# TTP.net
KiCad netlist of a schematic drawn in Altium Designer
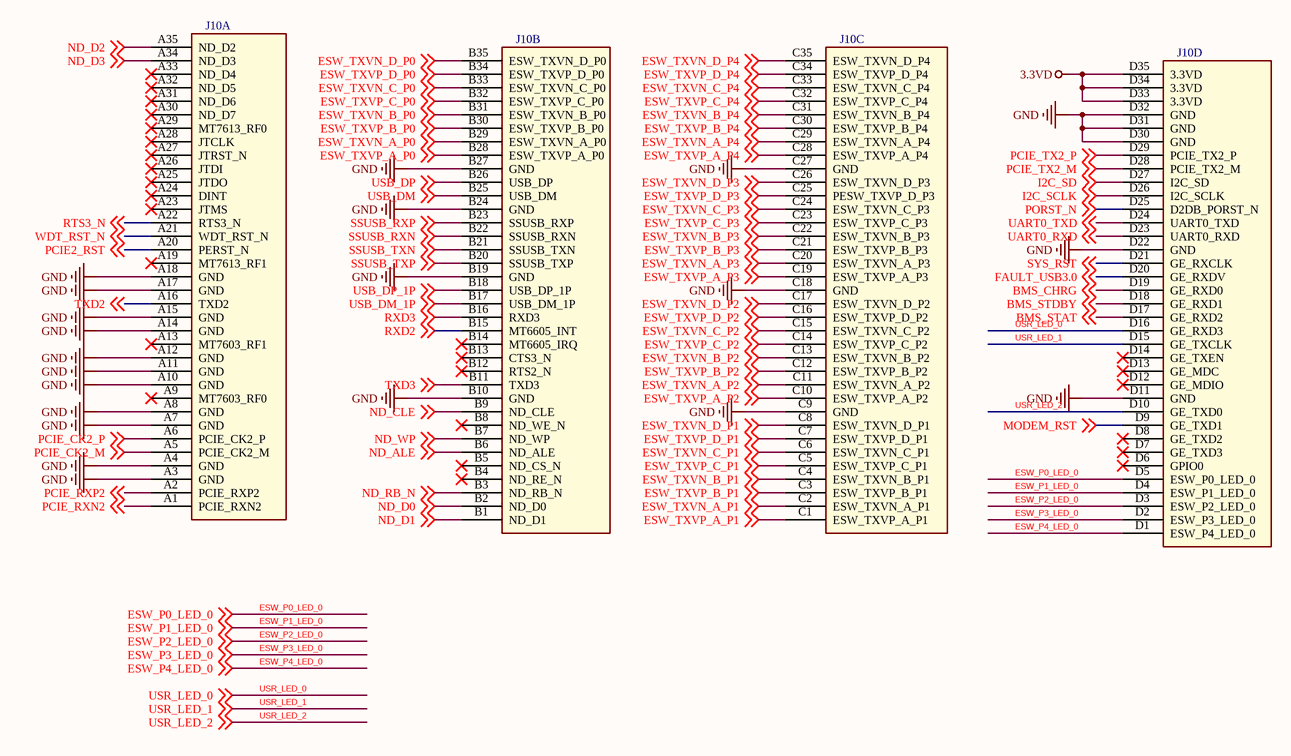
[diagram p0: TTP.SchDoc]

(export (version "E")
  (design (tool "Eeschema 10.0.6"))
  (components
    (comp (ref "J10") (value "SoM") (footprint "SoM") (libsource (lib "IIOT_GATEWAY_MT7621") (part "SoM")))
  )
  (nets
    (net (code "1") (name "3.3VD") (class "Default")
      (node (ref "J10") (pin "D33") (pinfunction "3.3VD_D33") (pintype "passive"))
      (node (ref "J10") (pin "D34") (pinfunction "3.3VD_D34") (pintype "passive"))
      (node (ref "J10") (pin "D35") (pinfunction "3.3VD_D35") (pintype "passive"))
    )
    (net (code "2") (name "BMS_CHRG") (class "Default")
      (node (ref "J10") (pin "D19") (pinfunction "GE_RXD0_D19") (pintype "passive"))
    )
    (net (code "3") (name "BMS_STAT") (class "Default")
      (node (ref "J10") (pin "D17") (pinfunction "GE_RXD2_D17") (pintype "passive"))
    )
    (net (code "4") (name "BMS_STDBY") (class "Default")
      (node (ref "J10") (pin "D18") (pinfunction "GE_RXD1_D18") (pintype "passive"))
    )
    (net (code "5") (name "ESW_P0_LED_0") (class "Default")
      (node (ref "J10") (pin "D5") (pinfunction "ESW_P0_LED_0_D5") (pintype "passive"))
    )
    (net (code "6") (name "ESW_P1_LED_0") (class "Default")
      (node (ref "J10") (pin "D4") (pinfunction "ESW_P1_LED_0_D4") (pintype "passive"))
    )
    (net (code "7") (name "ESW_P2_LED_0") (class "Default")
      (node (ref "J10") (pin "D3") (pinfunction "ESW_P2_LED_0_D3") (pintype "passive"))
    )
    (net (code "8") (name "ESW_P3_LED_0") (class "Default")
      (node (ref "J10") (pin "D2") (pinfunction "ESW_P3_LED_0_D2") (pintype "passive"))
    )
    (net (code "9") (name "ESW_P4_LED_0") (class "Default")
      (node (ref "J10") (pin "D1") (pinfunction "ESW_P4_LED_0_D1") (pintype "passive"))
    )
    (net (code "10") (name "ESW_TXVN_A_P0") (class "Default")
      (node (ref "J10") (pin "B29") (pinfunction "ESW_TXVN_A_P0_B29") (pintype "passive"))
    )
    (net (code "11") (name "ESW_TXVN_A_P1") (class "Default")
      (node (ref "J10") (pin "C2") (pinfunction "ESW_TXVN_A_P1_C2") (pintype "passive"))
    )
    (net (code "12") (name "ESW_TXVN_A_P2") (class "Default")
      (node (ref "J10") (pin "C11") (pinfunction "ESW_TXVN_A_P2_C11") (pintype "passive"))
    )
    (net (code "13") (name "ESW_TXVN_A_P3") (class "Default")
      (node (ref "J10") (pin "C20") (pinfunction "ESW_TXVN_A_P3_C20") (pintype "passive"))
    )
    (net (code "14") (name "ESW_TXVN_A_P4") (class "Default")
      (node (ref "J10") (pin "C29") (pinfunction "ESW_TXVN_A_P4_C29") (pintype "passive"))
    )
    (net (code "15") (name "ESW_TXVN_B_P0") (class "Default")
      (node (ref "J10") (pin "B31") (pinfunction "ESW_TXVN_B_P0_B31") (pintype "passive"))
    )
    (net (code "16") (name "ESW_TXVN_B_P1") (class "Default")
      (node (ref "J10") (pin "C4") (pinfunction "ESW_TXVN_B_P1_C4") (pintype "passive"))
    )
    (net (code "17") (name "ESW_TXVN_B_P2") (class "Default")
      (node (ref "J10") (pin "C13") (pinfunction "ESW_TXVN_B_P2_C13") (pintype "passive"))
    )
    (net (code "18") (name "ESW_TXVN_B_P3") (class "Default")
      (node (ref "J10") (pin "C22") (pinfunction "ESW_TXVN_B_P3_C22") (pintype "passive"))
    )
    (net (code "19") (name "ESW_TXVN_B_P4") (class "Default")
      (node (ref "J10") (pin "C31") (pinfunction "ESW_TXVN_B_P4_C31") (pintype "passive"))
    )
    (net (code "20") (name "ESW_TXVN_C_P0") (class "Default")
      (node (ref "J10") (pin "B33") (pinfunction "ESW_TXVN_C_P0_B33") (pintype "passive"))
    )
    (net (code "21") (name "ESW_TXVN_C_P1") (class "Default")
      (node (ref "J10") (pin "C6") (pinfunction "ESW_TXVN_C_P1_C6") (pintype "passive"))
    )
    (net (code "22") (name "ESW_TXVN_C_P2") (class "Default")
      (node (ref "J10") (pin "C15") (pinfunction "ESW_TXVN_C_P2_C15") (pintype "passive"))
    )
    (net (code "23") (name "ESW_TXVN_C_P3") (class "Default")
      (node (ref "J10") (pin "C24") (pinfunction "ESW_TXVN_C_P3_C24") (pintype "passive"))
    )
    (net (code "24") (name "ESW_TXVN_C_P4") (class "Default")
      (node (ref "J10") (pin "C33") (pinfunction "ESW_TXVN_C_P4_C33") (pintype "passive"))
    )
    (net (code "25") (name "ESW_TXVN_D_P0") (class "Default")
      (node (ref "J10") (pin "B35") (pinfunction "ESW_TXVN_D_P0_B35") (pintype "passive"))
    )
    (net (code "26") (name "ESW_TXVN_D_P1") (class "Default")
      (node (ref "J10") (pin "C8") (pinfunction "ESW_TXVN_D_P1_C8") (pintype "passive"))
    )
    (net (code "27") (name "ESW_TXVN_D_P2") (class "Default")
      (node (ref "J10") (pin "C17") (pinfunction "ESW_TXVN_D_P2_C17") (pintype "passive"))
    )
    (net (code "28") (name "ESW_TXVN_D_P3") (class "Default")
      (node (ref "J10") (pin "C26") (pinfunction "ESW_TXVN_D_P3_C26") (pintype "passive"))
    )
    (net (code "29") (name "ESW_TXVN_D_P4") (class "Default")
      (node (ref "J10") (pin "C35") (pinfunction "ESW_TXVN_D_P4_C35") (pintype "passive"))
    )
    (net (code "30") (name "ESW_TXVP_A_P0") (class "Default")
      (node (ref "J10") (pin "B28") (pinfunction "ESW_TXVP_A_P0_B28") (pintype "passive"))
    )
    (net (code "31") (name "ESW_TXVP_A_P1") (class "Default")
      (node (ref "J10") (pin "C1") (pinfunction "ESW_TXVP_A_P1_C1") (pintype "passive"))
    )
    (net (code "32") (name "ESW_TXVP_A_P2") (class "Default")
      (node (ref "J10") (pin "C10") (pinfunction "ESW_TXVP_A_P2_C10") (pintype "passive"))
    )
    (net (code "33") (name "ESW_TXVP_A_P3") (class "Default")
      (node (ref "J10") (pin "C19") (pinfunction "ESW_TXVP_A_P3_C19") (pintype "passive"))
    )
    (net (code "34") (name "ESW_TXVP_A_P4") (class "Default")
      (node (ref "J10") (pin "C28") (pinfunction "ESW_TXVP_A_P4_C28") (pintype "passive"))
    )
    (net (code "35") (name "ESW_TXVP_B_P0") (class "Default")
      (node (ref "J10") (pin "B30") (pinfunction "ESW_TXVP_B_P0_B30") (pintype "passive"))
    )
    (net (code "36") (name "ESW_TXVP_B_P1") (class "Default")
      (node (ref "J10") (pin "C3") (pinfunction "ESW_TXVP_B_P1_C3") (pintype "passive"))
    )
    (net (code "37") (name "ESW_TXVP_B_P2") (class "Default")
      (node (ref "J10") (pin "C12") (pinfunction "ESW_TXVP_B_P2_C12") (pintype "passive"))
    )
    (net (code "38") (name "ESW_TXVP_B_P3") (class "Default")
      (node (ref "J10") (pin "C21") (pinfunction "ESW_TXVP_B_P3_C21") (pintype "passive"))
    )
    (net (code "39") (name "ESW_TXVP_B_P4") (class "Default")
      (node (ref "J10") (pin "C30") (pinfunction "ESW_TXVP_B_P4_C30") (pintype "passive"))
    )
    (net (code "40") (name "ESW_TXVP_C_P0") (class "Default")
      (node (ref "J10") (pin "B32") (pinfunction "ESW_TXVP_C_P0_B32") (pintype "passive"))
    )
    (net (code "41") (name "ESW_TXVP_C_P1") (class "Default")
      (node (ref "J10") (pin "C5") (pinfunction "ESW_TXVP_C_P1_C5") (pintype "passive"))
    )
    (net (code "42") (name "ESW_TXVP_C_P2") (class "Default")
      (node (ref "J10") (pin "C14") (pinfunction "ESW_TXVP_C_P2_C14") (pintype "passive"))
    )
    (net (code "43") (name "ESW_TXVP_C_P3") (class "Default")
      (node (ref "J10") (pin "C23") (pinfunction "ESW_TXVP_C_P3_C23") (pintype "passive"))
    )
    (net (code "44") (name "ESW_TXVP_C_P4") (class "Default")
      (node (ref "J10") (pin "C32") (pinfunction "ESW_TXVP_C_P4_C32") (pintype "passive"))
    )
    (net (code "45") (name "ESW_TXVP_D_P0") (class "Default")
      (node (ref "J10") (pin "B34") (pinfunction "ESW_TXVP_D_P0_B34") (pintype "passive"))
    )
    (net (code "46") (name "ESW_TXVP_D_P1") (class "Default")
      (node (ref "J10") (pin "C7") (pinfunction "ESW_TXVP_D_P1_C7") (pintype "passive"))
    )
    (net (code "47") (name "ESW_TXVP_D_P2") (class "Default")
      (node (ref "J10") (pin "C16") (pinfunction "ESW_TXVP_D_P2_C16") (pintype "passive"))
    )
    (net (code "48") (name "ESW_TXVP_D_P3") (class "Default")
      (node (ref "J10") (pin "C25") (pinfunction "PESW_TXVP_D_P3_C25") (pintype "passive"))
    )
    (net (code "49") (name "ESW_TXVP_D_P4") (class "Default")
      (node (ref "J10") (pin "C34") (pinfunction "ESW_TXVP_D_P4_C34") (pintype "passive"))
    )
    (net (code "50") (name "FAULT_USB3.0") (class "Default")
      (node (ref "J10") (pin "D20") (pinfunction "GE_RXDV_D20") (pintype "passive"))
    )
    (net (code "51") (name "GND") (class "Default")
      (node (ref "J10") (pin "A10") (pinfunction "GND_A10") (pintype "passive"))
      (node (ref "J10") (pin "A11") (pinfunction "GND_A11") (pintype "passive"))
      (node (ref "J10") (pin "A12") (pinfunction "GND_A12") (pintype "passive"))
      (node (ref "J10") (pin "A14") (pinfunction "GND_A14") (pintype "passive"))
      (node (ref "J10") (pin "A15") (pinfunction "GND_A15") (pintype "passive"))
      (node (ref "J10") (pin "A17") (pinfunction "GND_A17") (pintype "passive"))
      (node (ref "J10") (pin "A18") (pinfunction "GND_A18") (pintype "passive"))
      (node (ref "J10") (pin "A3") (pinfunction "GND_A3") (pintype "passive"))
      (node (ref "J10") (pin "A4") (pinfunction "GND_A4") (pintype "passive"))
      (node (ref "J10") (pin "A7") (pinfunction "GND_A7") (pintype "passive"))
      (node (ref "J10") (pin "A8") (pinfunction "GND_A8") (pintype "passive"))
      (node (ref "J10") (pin "B10") (pinfunction "GND_B10") (pintype "passive"))
      (node (ref "J10") (pin "B19") (pinfunction "GND_B19") (pintype "passive"))
      (node (ref "J10") (pin "B24") (pinfunction "GND_B24") (pintype "passive"))
      (node (ref "J10") (pin "B27") (pinfunction "GND_B27") (pintype "passive"))
      (node (ref "J10") (pin "C18") (pinfunction "GND_C18") (pintype "passive"))
      (node (ref "J10") (pin "C27") (pinfunction "GND_C27") (pintype "passive"))
      (node (ref "J10") (pin "C9") (pinfunction "GND_C9") (pintype "passive"))
      (node (ref "J10") (pin "D11") (pinfunction "GND_D11") (pintype "passive"))
      (node (ref "J10") (pin "D22") (pinfunction "GND_D22") (pintype "passive"))
      (node (ref "J10") (pin "D30") (pinfunction "GND_D30") (pintype "passive"))
      (node (ref "J10") (pin "D31") (pinfunction "GND_D31") (pintype "passive"))
      (node (ref "J10") (pin "D32") (pinfunction "GND_D32") (pintype "passive"))
    )
    (net (code "52") (name "I2C_SCLK") (class "Default")
      (node (ref "J10") (pin "D26") (pinfunction "I2C_SCLK_D26") (pintype "passive"))
    )
    (net (code "53") (name "I2C_SD") (class "Default")
      (node (ref "J10") (pin "D27") (pinfunction "I2C_SD_D27") (pintype "passive"))
    )
    (net (code "54") (name "MODEM_RST") (class "Default")
      (node (ref "J10") (pin "D9") (pinfunction "GE_TXD1_D9") (pintype "passive"))
    )
    (net (code "55") (name "ND_ALE") (class "Default")
      (node (ref "J10") (pin "B6") (pinfunction "ND_ALE_B6") (pintype "passive"))
    )
    (net (code "56") (name "ND_CLE") (class "Default")
      (node (ref "J10") (pin "B9") (pinfunction "ND_CLE_B9") (pintype "passive"))
    )
    (net (code "57") (name "ND_D0") (class "Default")
      (node (ref "J10") (pin "B2") (pinfunction "ND_D0_B2") (pintype "passive"))
    )
    (net (code "58") (name "ND_D1") (class "Default")
      (node (ref "J10") (pin "B1") (pinfunction "ND_D1_B1") (pintype "passive"))
    )
    (net (code "59") (name "ND_D2") (class "Default")
      (node (ref "J10") (pin "A35") (pinfunction "ND_D2_A35") (pintype "passive"))
    )
    (net (code "60") (name "ND_D3") (class "Default")
      (node (ref "J10") (pin "A34") (pinfunction "ND_D3_A34") (pintype "passive"))
    )
    (net (code "61") (name "ND_RB_N") (class "Default")
      (node (ref "J10") (pin "B3") (pinfunction "ND_RB_N_B3") (pintype "passive"))
    )
    (net (code "62") (name "ND_WP") (class "Default")
      (node (ref "J10") (pin "B7") (pinfunction "ND_WP_B7") (pintype "passive"))
    )
    (net (code "63") (name "PCIE2_RST") (class "Default")
      (node (ref "J10") (pin "A20") (pinfunction "PERST_N_A20") (pintype "passive"))
    )
    (net (code "64") (name "PCIE_CK2_M") (class "Default")
      (node (ref "J10") (pin "A5") (pinfunction "PCIE_CK2_M_A5") (pintype "passive"))
    )
    (net (code "65") (name "PCIE_CK2_P") (class "Default")
      (node (ref "J10") (pin "A6") (pinfunction "PCIE_CK2_P_A6") (pintype "passive"))
    )
    (net (code "66") (name "PCIE_RXN2") (class "Default")
      (node (ref "J10") (pin "A1") (pinfunction "PCIE_RXN2_A1") (pintype "passive"))
    )
    (net (code "67") (name "PCIE_RXP2") (class "Default")
      (node (ref "J10") (pin "A2") (pinfunction "PCIE_RXP2_A2") (pintype "passive"))
    )
    (net (code "68") (name "PCIE_TX2_M") (class "Default")
      (node (ref "J10") (pin "D28") (pinfunction "PCIE_TX2_M_D28") (pintype "passive"))
    )
    (net (code "69") (name "PCIE_TX2_P") (class "Default")
      (node (ref "J10") (pin "D29") (pinfunction "PCIE_TX2_P_D29") (pintype "passive"))
    )
    (net (code "70") (name "PORST_N") (class "Default")
      (node (ref "J10") (pin "D25") (pinfunction "D2DB_PORST_N_D25") (pintype "passive"))
    )
    (net (code "71") (name "RTS3_N") (class "Default")
      (node (ref "J10") (pin "A22") (pinfunction "RTS3_N_A22") (pintype "passive"))
    )
    (net (code "72") (name "RXD2") (class "Default")
      (node (ref "J10") (pin "B15") (pinfunction "MT6605_INT_B15") (pintype "passive"))
    )
    (net (code "73") (name "RXD3") (class "Default")
      (node (ref "J10") (pin "B16") (pinfunction "RXD3_B16") (pintype "passive"))
    )
    (net (code "74") (name "SSUSB_RXN") (class "Default")
      (node (ref "J10") (pin "B22") (pinfunction "SSUSB_RXN_B22") (pintype "passive"))
    )
    (net (code "75") (name "SSUSB_RXP") (class "Default")
      (node (ref "J10") (pin "B23") (pinfunction "SSUSB_RXP_B23") (pintype "passive"))
    )
    (net (code "76") (name "SSUSB_TXN") (class "Default")
      (node (ref "J10") (pin "B21") (pinfunction "SSUSB_TXN_B21") (pintype "passive"))
    )
    (net (code "77") (name "SSUSB_TXP") (class "Default")
      (node (ref "J10") (pin "B20") (pinfunction "SSUSB_TXP_B20") (pintype "passive"))
    )
    (net (code "78") (name "SYS_RST") (class "Default")
      (node (ref "J10") (pin "D21") (pinfunction "GE_RXCLK_D21") (pintype "passive"))
    )
    (net (code "79") (name "TXD2") (class "Default")
      (node (ref "J10") (pin "A16") (pinfunction "TXD2_A16") (pintype "passive"))
    )
    (net (code "80") (name "TXD3") (class "Default")
      (node (ref "J10") (pin "B11") (pinfunction "TXD3_B11") (pintype "passive"))
    )
    (net (code "81") (name "UART0_RXD") (class "Default")
      (node (ref "J10") (pin "D23") (pinfunction "UART0_RXD_D23") (pintype "passive"))
    )
    (net (code "82") (name "UART0_TXD") (class "Default")
      (node (ref "J10") (pin "D24") (pinfunction "UART0_TXD_D24") (pintype "passive"))
    )
    (net (code "83") (name "USB_DM") (class "Default")
      (node (ref "J10") (pin "B25") (pinfunction "USB_DM_B25") (pintype "passive"))
    )
    (net (code "84") (name "USB_DM_1P") (class "Default")
      (node (ref "J10") (pin "B17") (pinfunction "USB_DM_1P_B17") (pintype "passive"))
    )
    (net (code "85") (name "USB_DP") (class "Default")
      (node (ref "J10") (pin "B26") (pinfunction "USB_DP_B26") (pintype "passive"))
    )
    (net (code "86") (name "USB_DP_1P") (class "Default")
      (node (ref "J10") (pin "B18") (pinfunction "USB_DP_1P_B18") (pintype "passive"))
    )
    (net (code "87") (name "USR_LED_0") (class "Default")
      (node (ref "J10") (pin "D16") (pinfunction "GE_RXD3_D16") (pintype "passive"))
    )
    (net (code "88") (name "USR_LED_1") (class "Default")
      (node (ref "J10") (pin "D15") (pinfunction "GE_TXCLK_D15") (pintype "passive"))
    )
    (net (code "89") (name "USR_LED_2") (class "Default")
      (node (ref "J10") (pin "D10") (pinfunction "GE_TXD0_D10") (pintype "passive"))
    )
    (net (code "90") (name "WDT_RST_N") (class "Default")
      (node (ref "J10") (pin "A21") (pinfunction "WDT_RST_N_A21") (pintype "passive"))
    )
    (net (code "91") (name "unconnected-(J10A-DINT-PadA24)") (class "Default")
      (node (ref "J10") (pin "A24") (pinfunction "DINT_A24") (pintype "passive+no_connect"))
    )
    (net (code "92") (name "unconnected-(J10A-JTCLK-PadA28)") (class "Default")
      (node (ref "J10") (pin "A28") (pinfunction "JTCLK_A28") (pintype "passive+no_connect"))
    )
    (net (code "93") (name "unconnected-(J10A-JTDI-PadA26)") (class "Default")
      (node (ref "J10") (pin "A26") (pinfunction "JTDI_A26") (pintype "passive+no_connect"))
    )
    (net (code "94") (name "unconnected-(J10A-JTDO-PadA25)") (class "Default")
      (node (ref "J10") (pin "A25") (pinfunction "JTDO_A25") (pintype "passive+no_connect"))
    )
    (net (code "95") (name "unconnected-(J10A-JTMS-PadA23)") (class "Default")
      (node (ref "J10") (pin "A23") (pinfunction "JTMS_A23") (pintype "passive+no_connect"))
    )
    (net (code "96") (name "unconnected-(J10A-JTRST_N-PadA27)") (class "Default")
      (node (ref "J10") (pin "A27") (pinfunction "JTRST_N_A27") (pintype "passive+no_connect"))
    )
    (net (code "97") (name "unconnected-(J10A-MT7603_RF0-PadA9)") (class "Default")
      (node (ref "J10") (pin "A9") (pinfunction "MT7603_RF0_A9") (pintype "passive+no_connect"))
    )
    (net (code "98") (name "unconnected-(J10A-MT7603_RF1-PadA13)") (class "Default")
      (node (ref "J10") (pin "A13") (pinfunction "MT7603_RF1_A13") (pintype "passive+no_connect"))
    )
    (net (code "99") (name "unconnected-(J10A-MT7613_RF0-PadA29)") (class "Default")
      (node (ref "J10") (pin "A29") (pinfunction "MT7613_RF0_A29") (pintype "passive+no_connect"))
    )
    (net (code "100") (name "unconnected-(J10A-MT7613_RF1-PadA19)") (class "Default")
      (node (ref "J10") (pin "A19") (pinfunction "MT7613_RF1_A19") (pintype "passive+no_connect"))
    )
    (net (code "101") (name "unconnected-(J10A-ND_D4-PadA33)") (class "Default")
      (node (ref "J10") (pin "A33") (pinfunction "ND_D4_A33") (pintype "passive+no_connect"))
    )
    (net (code "102") (name "unconnected-(J10A-ND_D5-PadA32)") (class "Default")
      (node (ref "J10") (pin "A32") (pinfunction "ND_D5_A32") (pintype "passive+no_connect"))
    )
    (net (code "103") (name "unconnected-(J10A-ND_D6-PadA31)") (class "Default")
      (node (ref "J10") (pin "A31") (pinfunction "ND_D6_A31") (pintype "passive+no_connect"))
    )
    (net (code "104") (name "unconnected-(J10A-ND_D7-PadA30)") (class "Default")
      (node (ref "J10") (pin "A30") (pinfunction "ND_D7_A30") (pintype "passive+no_connect"))
    )
    (net (code "105") (name "unconnected-(J10B-CTS3_N-PadB13)") (class "Default")
      (node (ref "J10") (pin "B13") (pinfunction "CTS3_N_B13") (pintype "passive+no_connect"))
    )
    (net (code "106") (name "unconnected-(J10B-MT6605_IRQ-PadB14)") (class "Default")
      (node (ref "J10") (pin "B14") (pinfunction "MT6605_IRQ_B14") (pintype "passive+no_connect"))
    )
    (net (code "107") (name "unconnected-(J10B-ND_CS_N-PadB5)") (class "Default")
      (node (ref "J10") (pin "B5") (pinfunction "ND_CS_N_B5") (pintype "passive+no_connect"))
    )
    (net (code "108") (name "unconnected-(J10B-ND_RE_N-PadB4)") (class "Default")
      (node (ref "J10") (pin "B4") (pinfunction "ND_RE_N_B4") (pintype "passive+no_connect"))
    )
    (net (code "109") (name "unconnected-(J10B-ND_WE_N-PadB8)") (class "Default")
      (node (ref "J10") (pin "B8") (pinfunction "ND_WE_N_B8") (pintype "passive+no_connect"))
    )
    (net (code "110") (name "unconnected-(J10B-RTS2_N-PadB12)") (class "Default")
      (node (ref "J10") (pin "B12") (pinfunction "RTS2_N_B12") (pintype "passive+no_connect"))
    )
    (net (code "111") (name "unconnected-(J10D-GE_MDC-PadD13)") (class "Default")
      (node (ref "J10") (pin "D13") (pinfunction "GE_MDC_D13") (pintype "passive+no_connect"))
    )
    (net (code "112") (name "unconnected-(J10D-GE_MDIO-PadD12)") (class "Default")
      (node (ref "J10") (pin "D12") (pinfunction "GE_MDIO_D12") (pintype "passive+no_connect"))
    )
    (net (code "113") (name "unconnected-(J10D-GE_TXD2-PadD8)") (class "Default")
      (node (ref "J10") (pin "D8") (pinfunction "GE_TXD2_D8") (pintype "passive+no_connect"))
    )
    (net (code "114") (name "unconnected-(J10D-GE_TXD3-PadD7)") (class "Default")
      (node (ref "J10") (pin "D7") (pinfunction "GE_TXD3_D7") (pintype "passive+no_connect"))
    )
    (net (code "115") (name "unconnected-(J10D-GE_TXEN-PadD14)") (class "Default")
      (node (ref "J10") (pin "D14") (pinfunction "GE_TXEN_D14") (pintype "passive+no_connect"))
    )
    (net (code "116") (name "unconnected-(J10D-GPIO0-PadD6)") (class "Default")
      (node (ref "J10") (pin "D6") (pinfunction "GPIO0_D6") (pintype "passive+no_connect"))
    )
  )
)
